# 09-_CAN.net
KiCad netlist of a schematic drawn in Altium Designer
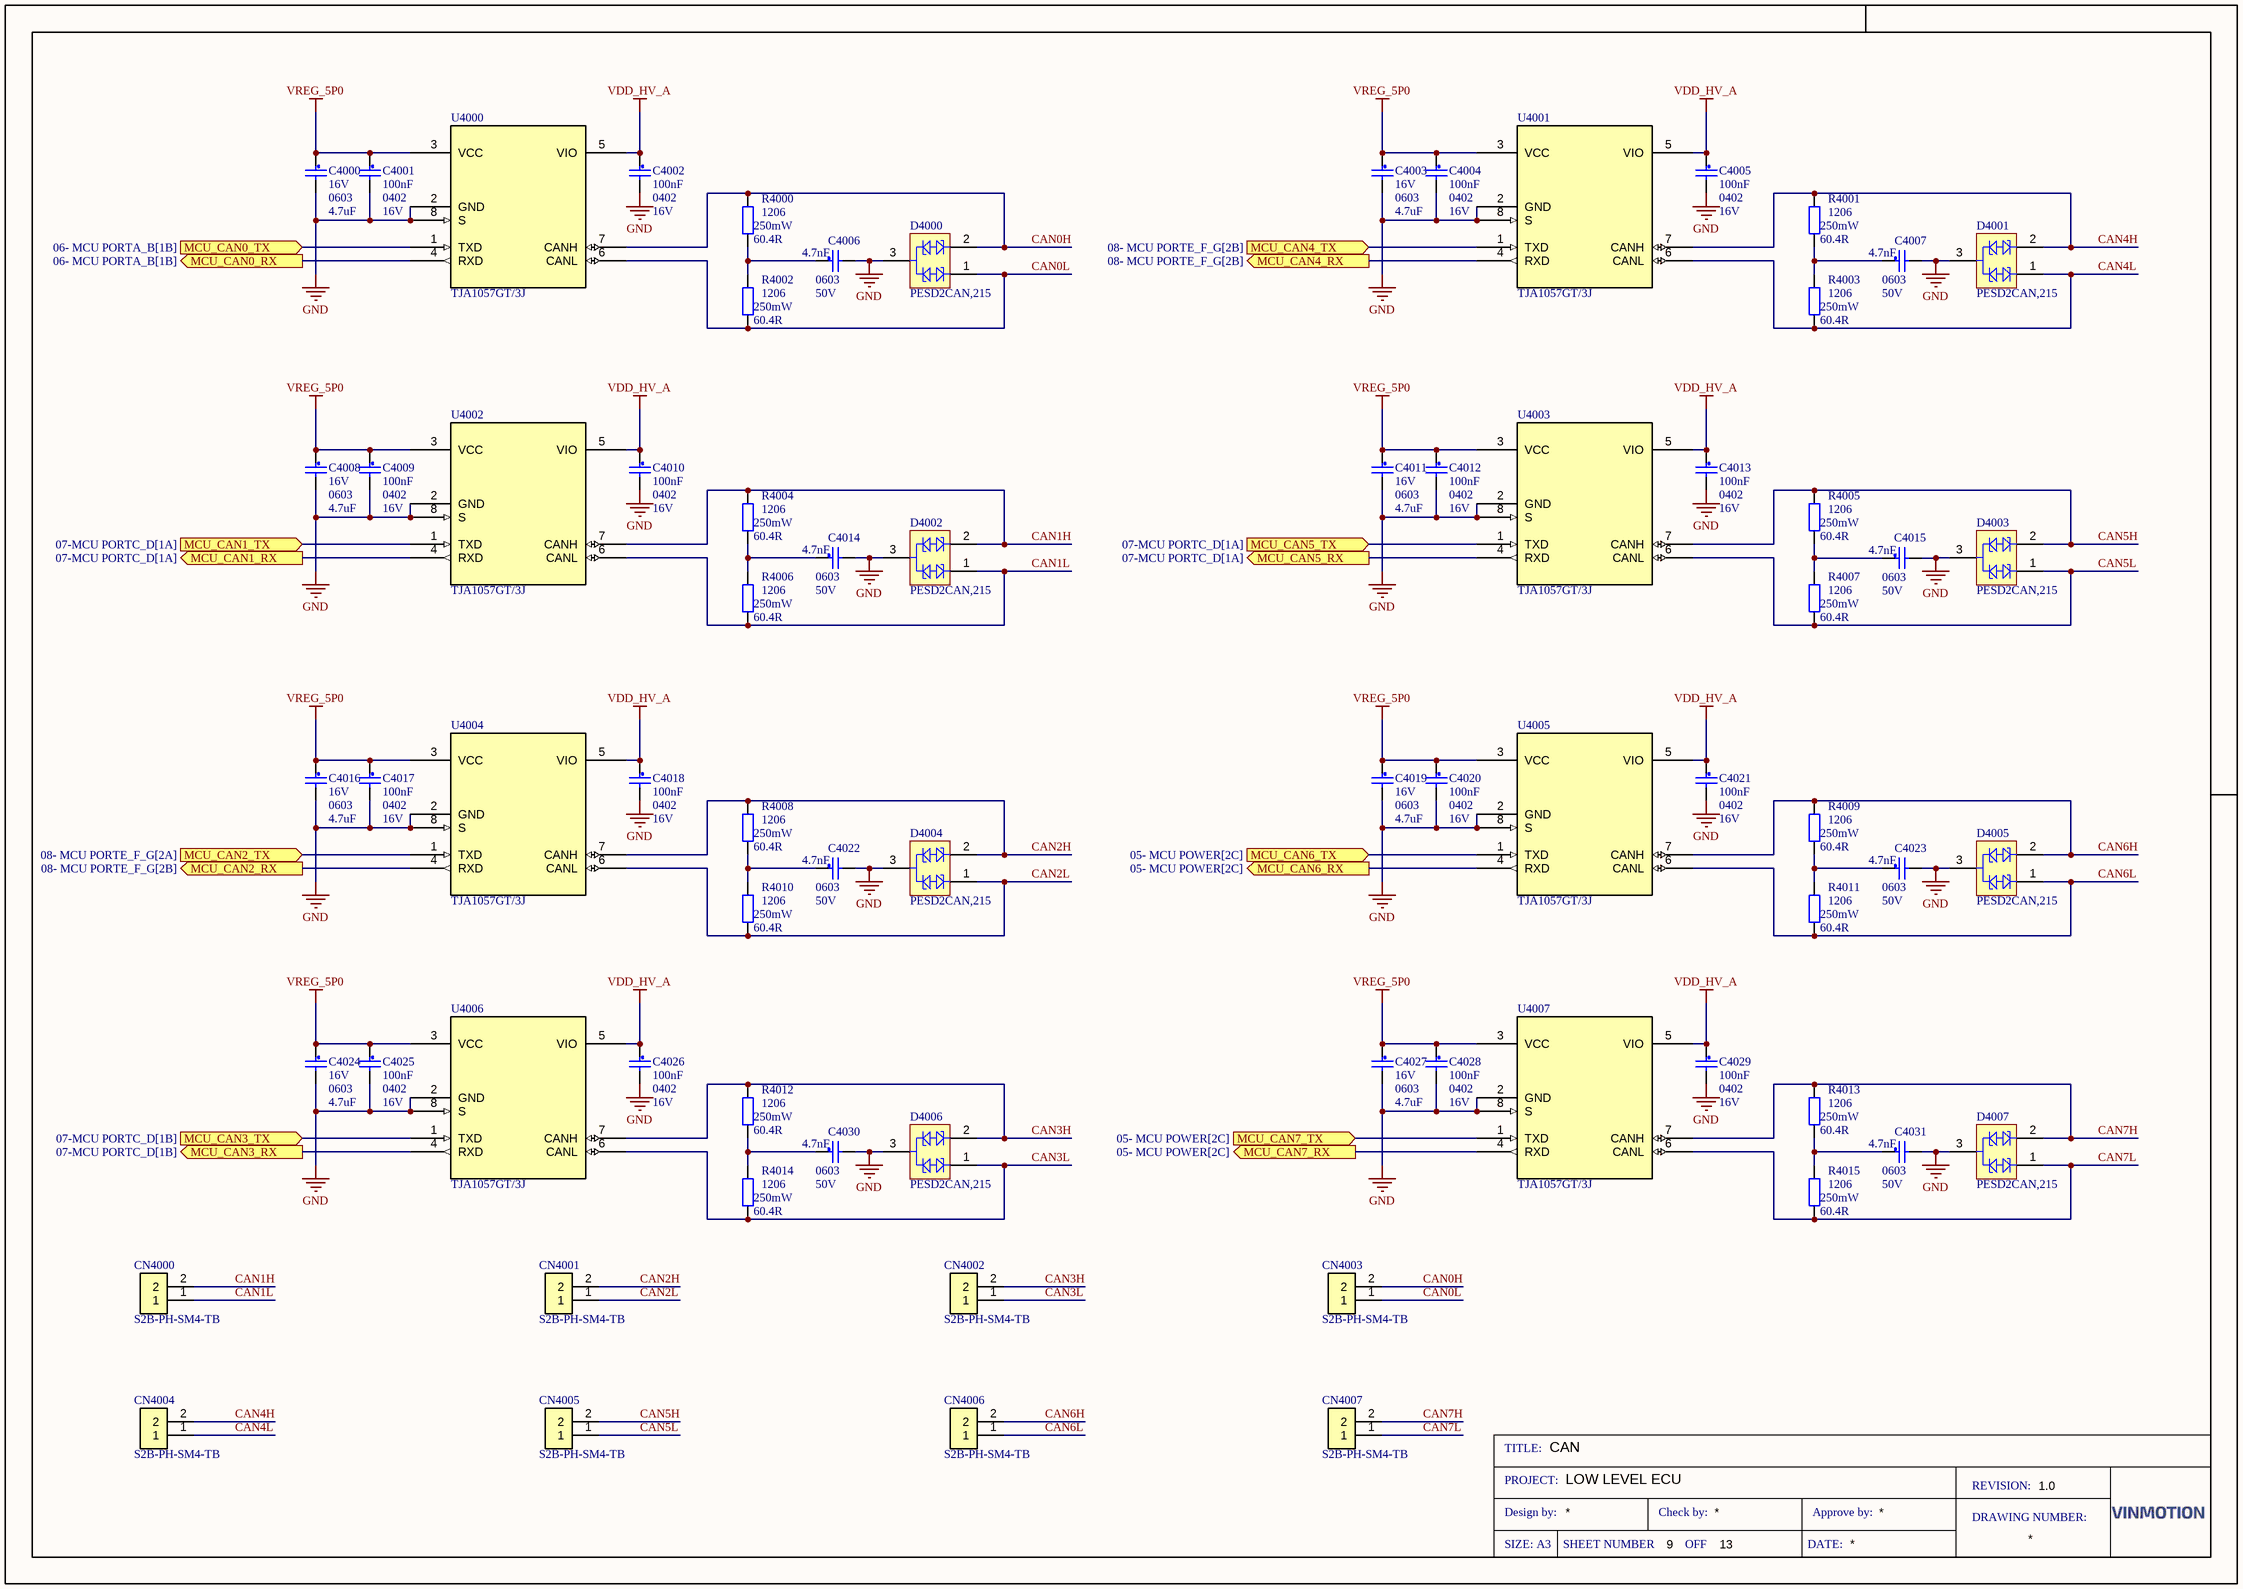
[diagram p0: 09- CAN.SchDoc]

(export (version "E")
  (design (tool "Eeschema 10.0.6"))
  (components
    (comp (ref "C4000")
      (value "GRT188C81C475KE13D")
      (footprint "CAP0603")
      (description "CAP CER 4.7uF 16V 10% X6S 0603 SMD")
      (fields
        (field (name "TOLERANCE") "10%")
        (field (name "VOLTAGE RATING") "16V")
        (field (name "CASE/PACKAGE") "0603")
        (field (name "CAPACITANCE") "4.7uF")
      )
      (libsource (lib "VMO_Lib") (part "CMP-00351-2"))
    )
    (comp (ref "C4001")
      (value "0402YC104KAT2A")
      (footprint "CAP0402")
      (description "CAP CER 0.1UF 16V X7R 0402")
      (fields
        (field (name "CAPACITANCE") "100nF")
        (field (name "CASE/PACKAGE") "0402")
        (field (name "VOLTAGE RATING (DC)") "16V")
      )
      (libsource (lib "VMO_Lib") (part "CMP-00988-1"))
    )
    (comp (ref "C4002")
      (value "0402YC104KAT2A")
      (footprint "CAP0402")
      (description "CAP CER 0.1UF 16V X7R 0402")
      (fields
        (field (name "CAPACITANCE") "100nF")
        (field (name "CASE/PACKAGE") "0402")
        (field (name "VOLTAGE RATING (DC)") "16V")
      )
      (libsource (lib "VMO_Lib") (part "CMP-00988-1"))
    )
    (comp (ref "C4003")
      (value "GRT188C81C475KE13D")
      (footprint "CAP0603")
      (description "CAP CER 4.7uF 16V 10% X6S 0603 SMD")
      (fields
        (field (name "TOLERANCE") "10%")
        (field (name "VOLTAGE RATING") "16V")
        (field (name "CASE/PACKAGE") "0603")
        (field (name "CAPACITANCE") "4.7uF")
      )
      (libsource (lib "VMO_Lib") (part "CMP-00351-2"))
    )
    (comp (ref "C4004")
      (value "0402YC104KAT2A")
      (footprint "CAP0402")
      (description "CAP CER 0.1UF 16V X7R 0402")
      (fields
        (field (name "CAPACITANCE") "100nF")
        (field (name "CASE/PACKAGE") "0402")
        (field (name "VOLTAGE RATING (DC)") "16V")
      )
      (libsource (lib "VMO_Lib") (part "CMP-00988-1"))
    )
    (comp (ref "C4005")
      (value "0402YC104KAT2A")
      (footprint "CAP0402")
      (description "CAP CER 0.1UF 16V X7R 0402")
      (fields
        (field (name "CAPACITANCE") "100nF")
        (field (name "CASE/PACKAGE") "0402")
        (field (name "VOLTAGE RATING (DC)") "16V")
      )
      (libsource (lib "VMO_Lib") (part "CMP-00988-1"))
    )
    (comp (ref "C4006")
      (value "CL10B472KB8WPNC")
      (footprint "CAP0603")
      (description "CAP CER 4700PF 50V X7R 0603")
      (fields
        (field (name "TOLERANCE") "10%")
        (field (name "CASE CODE (IMPERIAL)") "0603")
        (field (name "VOLTAGE RATING") "50V")
        (field (name "CAPACITANCE") "4.7nF")
      )
      (libsource (lib "VMO_Lib") (part "CMP-00892-1"))
    )
    (comp (ref "C4007")
      (value "CL10B472KB8WPNC")
      (footprint "CAP0603")
      (description "CAP CER 4700PF 50V X7R 0603")
      (fields
        (field (name "TOLERANCE") "10%")
        (field (name "CASE CODE (IMPERIAL)") "0603")
        (field (name "VOLTAGE RATING") "50V")
        (field (name "CAPACITANCE") "4.7nF")
      )
      (libsource (lib "VMO_Lib") (part "CMP-00892-1"))
    )
    (comp (ref "C4008")
      (value "GRT188C81C475KE13D")
      (footprint "CAP0603")
      (description "CAP CER 4.7uF 16V 10% X6S 0603 SMD")
      (fields
        (field (name "TOLERANCE") "10%")
        (field (name "VOLTAGE RATING") "16V")
        (field (name "CASE/PACKAGE") "0603")
        (field (name "CAPACITANCE") "4.7uF")
      )
      (libsource (lib "VMO_Lib") (part "CMP-00351-2"))
    )
    (comp (ref "C4009")
      (value "0402YC104KAT2A")
      (footprint "CAP0402")
      (description "CAP CER 0.1UF 16V X7R 0402")
      (fields
        (field (name "CAPACITANCE") "100nF")
        (field (name "CASE/PACKAGE") "0402")
        (field (name "VOLTAGE RATING (DC)") "16V")
      )
      (libsource (lib "VMO_Lib") (part "CMP-00988-1"))
    )
    (comp (ref "C4010")
      (value "0402YC104KAT2A")
      (footprint "CAP0402")
      (description "CAP CER 0.1UF 16V X7R 0402")
      (fields
        (field (name "CAPACITANCE") "100nF")
        (field (name "CASE/PACKAGE") "0402")
        (field (name "VOLTAGE RATING (DC)") "16V")
      )
      (libsource (lib "VMO_Lib") (part "CMP-00988-1"))
    )
    (comp (ref "C4011")
      (value "GRT188C81C475KE13D")
      (footprint "CAP0603")
      (description "CAP CER 4.7uF 16V 10% X6S 0603 SMD")
      (fields
        (field (name "TOLERANCE") "10%")
        (field (name "VOLTAGE RATING") "16V")
        (field (name "CASE/PACKAGE") "0603")
        (field (name "CAPACITANCE") "4.7uF")
      )
      (libsource (lib "VMO_Lib") (part "CMP-00351-2"))
    )
    (comp (ref "C4012")
      (value "0402YC104KAT2A")
      (footprint "CAP0402")
      (description "CAP CER 0.1UF 16V X7R 0402")
      (fields
        (field (name "CAPACITANCE") "100nF")
        (field (name "CASE/PACKAGE") "0402")
        (field (name "VOLTAGE RATING (DC)") "16V")
      )
      (libsource (lib "VMO_Lib") (part "CMP-00988-1"))
    )
    (comp (ref "C4013")
      (value "0402YC104KAT2A")
      (footprint "CAP0402")
      (description "CAP CER 0.1UF 16V X7R 0402")
      (fields
        (field (name "CAPACITANCE") "100nF")
        (field (name "CASE/PACKAGE") "0402")
        (field (name "VOLTAGE RATING (DC)") "16V")
      )
      (libsource (lib "VMO_Lib") (part "CMP-00988-1"))
    )
    (comp (ref "C4014")
      (value "CL10B472KB8WPNC")
      (footprint "CAP0603")
      (description "CAP CER 4700PF 50V X7R 0603")
      (fields
        (field (name "TOLERANCE") "10%")
        (field (name "CASE CODE (IMPERIAL)") "0603")
        (field (name "VOLTAGE RATING") "50V")
        (field (name "CAPACITANCE") "4.7nF")
      )
      (libsource (lib "VMO_Lib") (part "CMP-00892-1"))
    )
    (comp (ref "C4015")
      (value "CL10B472KB8WPNC")
      (footprint "CAP0603")
      (description "CAP CER 4700PF 50V X7R 0603")
      (fields
        (field (name "TOLERANCE") "10%")
        (field (name "CASE CODE (IMPERIAL)") "0603")
        (field (name "VOLTAGE RATING") "50V")
        (field (name "CAPACITANCE") "4.7nF")
      )
      (libsource (lib "VMO_Lib") (part "CMP-00892-1"))
    )
    (comp (ref "C4016")
      (value "GRT188C81C475KE13D")
      (footprint "CAP0603")
      (description "CAP CER 4.7uF 16V 10% X6S 0603 SMD")
      (fields
        (field (name "TOLERANCE") "10%")
        (field (name "VOLTAGE RATING") "16V")
        (field (name "CASE/PACKAGE") "0603")
        (field (name "CAPACITANCE") "4.7uF")
      )
      (libsource (lib "VMO_Lib") (part "CMP-00351-2"))
    )
    (comp (ref "C4017")
      (value "0402YC104KAT2A")
      (footprint "CAP0402")
      (description "CAP CER 0.1UF 16V X7R 0402")
      (fields
        (field (name "CAPACITANCE") "100nF")
        (field (name "CASE/PACKAGE") "0402")
        (field (name "VOLTAGE RATING (DC)") "16V")
      )
      (libsource (lib "VMO_Lib") (part "CMP-00988-1"))
    )
    (comp (ref "C4018")
      (value "0402YC104KAT2A")
      (footprint "CAP0402")
      (description "CAP CER 0.1UF 16V X7R 0402")
      (fields
        (field (name "CAPACITANCE") "100nF")
        (field (name "CASE/PACKAGE") "0402")
        (field (name "VOLTAGE RATING (DC)") "16V")
      )
      (libsource (lib "VMO_Lib") (part "CMP-00988-1"))
    )
    (comp (ref "C4019")
      (value "GRT188C81C475KE13D")
      (footprint "CAP0603")
      (description "CAP CER 4.7uF 16V 10% X6S 0603 SMD")
      (fields
        (field (name "TOLERANCE") "10%")
        (field (name "VOLTAGE RATING") "16V")
        (field (name "CASE/PACKAGE") "0603")
        (field (name "CAPACITANCE") "4.7uF")
      )
      (libsource (lib "VMO_Lib") (part "CMP-00351-2"))
    )
    (comp (ref "C4020")
      (value "0402YC104KAT2A")
      (footprint "CAP0402")
      (description "CAP CER 0.1UF 16V X7R 0402")
      (fields
        (field (name "CAPACITANCE") "100nF")
        (field (name "CASE/PACKAGE") "0402")
        (field (name "VOLTAGE RATING (DC)") "16V")
      )
      (libsource (lib "VMO_Lib") (part "CMP-00988-1"))
    )
    (comp (ref "C4021")
      (value "0402YC104KAT2A")
      (footprint "CAP0402")
      (description "CAP CER 0.1UF 16V X7R 0402")
      (fields
        (field (name "CAPACITANCE") "100nF")
        (field (name "CASE/PACKAGE") "0402")
        (field (name "VOLTAGE RATING (DC)") "16V")
      )
      (libsource (lib "VMO_Lib") (part "CMP-00988-1"))
    )
    (comp (ref "C4022")
      (value "CL10B472KB8WPNC")
      (footprint "CAP0603")
      (description "CAP CER 4700PF 50V X7R 0603")
      (fields
        (field (name "TOLERANCE") "10%")
        (field (name "CASE CODE (IMPERIAL)") "0603")
        (field (name "VOLTAGE RATING") "50V")
        (field (name "CAPACITANCE") "4.7nF")
      )
      (libsource (lib "VMO_Lib") (part "CMP-00892-1"))
    )
    (comp (ref "C4023")
      (value "CL10B472KB8WPNC")
      (footprint "CAP0603")
      (description "CAP CER 4700PF 50V X7R 0603")
      (fields
        (field (name "TOLERANCE") "10%")
        (field (name "CASE CODE (IMPERIAL)") "0603")
        (field (name "VOLTAGE RATING") "50V")
        (field (name "CAPACITANCE") "4.7nF")
      )
      (libsource (lib "VMO_Lib") (part "CMP-00892-1"))
    )
    (comp (ref "C4024")
      (value "GRT188C81C475KE13D")
      (footprint "CAP0603")
      (description "CAP CER 4.7uF 16V 10% X6S 0603 SMD")
      (fields
        (field (name "TOLERANCE") "10%")
        (field (name "VOLTAGE RATING") "16V")
        (field (name "CASE/PACKAGE") "0603")
        (field (name "CAPACITANCE") "4.7uF")
      )
      (libsource (lib "VMO_Lib") (part "CMP-00351-2"))
    )
    (comp (ref "C4025")
      (value "0402YC104KAT2A")
      (footprint "CAP0402")
      (description "CAP CER 0.1UF 16V X7R 0402")
      (fields
        (field (name "CAPACITANCE") "100nF")
        (field (name "CASE/PACKAGE") "0402")
        (field (name "VOLTAGE RATING (DC)") "16V")
      )
      (libsource (lib "VMO_Lib") (part "CMP-00988-1"))
    )
    (comp (ref "C4026")
      (value "0402YC104KAT2A")
      (footprint "CAP0402")
      (description "CAP CER 0.1UF 16V X7R 0402")
      (fields
        (field (name "CAPACITANCE") "100nF")
        (field (name "CASE/PACKAGE") "0402")
        (field (name "VOLTAGE RATING (DC)") "16V")
      )
      (libsource (lib "VMO_Lib") (part "CMP-00988-1"))
    )
    (comp (ref "C4027")
      (value "GRT188C81C475KE13D")
      (footprint "CAP0603")
      (description "CAP CER 4.7uF 16V 10% X6S 0603 SMD")
      (fields
        (field (name "TOLERANCE") "10%")
        (field (name "VOLTAGE RATING") "16V")
        (field (name "CASE/PACKAGE") "0603")
        (field (name "CAPACITANCE") "4.7uF")
      )
      (libsource (lib "VMO_Lib") (part "CMP-00351-2"))
    )
    (comp (ref "C4028")
      (value "0402YC104KAT2A")
      (footprint "CAP0402")
      (description "CAP CER 0.1UF 16V X7R 0402")
      (fields
        (field (name "CAPACITANCE") "100nF")
        (field (name "CASE/PACKAGE") "0402")
        (field (name "VOLTAGE RATING (DC)") "16V")
      )
      (libsource (lib "VMO_Lib") (part "CMP-00988-1"))
    )
    (comp (ref "C4029")
      (value "0402YC104KAT2A")
      (footprint "CAP0402")
      (description "CAP CER 0.1UF 16V X7R 0402")
      (fields
        (field (name "CAPACITANCE") "100nF")
        (field (name "CASE/PACKAGE") "0402")
        (field (name "VOLTAGE RATING (DC)") "16V")
      )
      (libsource (lib "VMO_Lib") (part "CMP-00988-1"))
    )
    (comp (ref "C4030")
      (value "CL10B472KB8WPNC")
      (footprint "CAP0603")
      (description "CAP CER 4700PF 50V X7R 0603")
      (fields
        (field (name "TOLERANCE") "10%")
        (field (name "CASE CODE (IMPERIAL)") "0603")
        (field (name "VOLTAGE RATING") "50V")
        (field (name "CAPACITANCE") "4.7nF")
      )
      (libsource (lib "VMO_Lib") (part "CMP-00892-1"))
    )
    (comp (ref "C4031")
      (value "CL10B472KB8WPNC")
      (footprint "CAP0603")
      (description "CAP CER 4700PF 50V X7R 0603")
      (fields
        (field (name "TOLERANCE") "10%")
        (field (name "CASE CODE (IMPERIAL)") "0603")
        (field (name "VOLTAGE RATING") "50V")
        (field (name "CAPACITANCE") "4.7nF")
      )
      (libsource (lib "VMO_Lib") (part "CMP-00892-1"))
    )
    (comp (ref "CN4000")
      (value "S2B-PH-SM4-TB")
      (footprint "S2B-PH-SM4-TB")
      (description "CONN HEADER SMD R/A 2POS 2MM")
      (fields (field (name "MANUFACTURER") "JST") (field (name "MANUFACTURER PART NUMBER") "S2BPHSM4TBLFSN"))
      (libsource (lib "VMO_Lib") (part "CMP-01142-1"))
    )
    (comp (ref "CN4001")
      (value "S2B-PH-SM4-TB")
      (footprint "S2B-PH-SM4-TB")
      (description "CONN HEADER SMD R/A 2POS 2MM")
      (fields (field (name "MANUFACTURER") "JST") (field (name "MANUFACTURER PART NUMBER") "S2BPHSM4TBLFSN"))
      (libsource (lib "VMO_Lib") (part "CMP-01142-1"))
    )
    (comp (ref "CN4002")
      (value "S2B-PH-SM4-TB")
      (footprint "S2B-PH-SM4-TB")
      (description "CONN HEADER SMD R/A 2POS 2MM")
      (fields (field (name "MANUFACTURER") "JST") (field (name "MANUFACTURER PART NUMBER") "S2BPHSM4TBLFSN"))
      (libsource (lib "VMO_Lib") (part "CMP-01142-1"))
    )
    (comp (ref "CN4003")
      (value "S2B-PH-SM4-TB")
      (footprint "S2B-PH-SM4-TB")
      (description "CONN HEADER SMD R/A 2POS 2MM")
      (fields (field (name "MANUFACTURER") "JST") (field (name "MANUFACTURER PART NUMBER") "S2BPHSM4TBLFSN"))
      (libsource (lib "VMO_Lib") (part "CMP-01142-1"))
    )
    (comp (ref "CN4004")
      (value "S2B-PH-SM4-TB")
      (footprint "S2B-PH-SM4-TB")
      (description "CONN HEADER SMD R/A 2POS 2MM")
      (fields (field (name "MANUFACTURER") "JST") (field (name "MANUFACTURER PART NUMBER") "S2BPHSM4TBLFSN"))
      (libsource (lib "VMO_Lib") (part "CMP-01142-1"))
    )
    (comp (ref "CN4005")
      (value "S2B-PH-SM4-TB")
      (footprint "S2B-PH-SM4-TB")
      (description "CONN HEADER SMD R/A 2POS 2MM")
      (fields (field (name "MANUFACTURER") "JST") (field (name "MANUFACTURER PART NUMBER") "S2BPHSM4TBLFSN"))
      (libsource (lib "VMO_Lib") (part "CMP-01142-1"))
    )
    (comp (ref "CN4006")
      (value "S2B-PH-SM4-TB")
      (footprint "S2B-PH-SM4-TB")
      (description "CONN HEADER SMD R/A 2POS 2MM")
      (fields (field (name "MANUFACTURER") "JST") (field (name "MANUFACTURER PART NUMBER") "S2BPHSM4TBLFSN"))
      (libsource (lib "VMO_Lib") (part "CMP-01142-1"))
    )
    (comp (ref "CN4007")
      (value "S2B-PH-SM4-TB")
      (footprint "S2B-PH-SM4-TB")
      (description "CONN HEADER SMD R/A 2POS 2MM")
      (fields (field (name "MANUFACTURER") "JST") (field (name "MANUFACTURER PART NUMBER") "S2BPHSM4TBLFSN"))
      (libsource (lib "VMO_Lib") (part "CMP-01142-1"))
    )
    (comp (ref "D4000")
      (value "PESD2CAN,215")
      (footprint "NEXPERIA_PESD2CAN,215_N")
      (description "DIODE TVS 24VWM 41VC SOT-23-3")
      (libsource (lib "VMO_Lib") (part "CMP-ROOT-0006-8"))
    )
    (comp (ref "D4001")
      (value "PESD2CAN,215")
      (footprint "NEXPERIA_PESD2CAN,215_N")
      (description "DIODE TVS 24VWM 41VC SOT-23-3")
      (libsource (lib "VMO_Lib") (part "CMP-ROOT-0006-8"))
    )
    (comp (ref "D4002")
      (value "PESD2CAN,215")
      (footprint "NEXPERIA_PESD2CAN,215_N")
      (description "DIODE TVS 24VWM 41VC SOT-23-3")
      (libsource (lib "VMO_Lib") (part "CMP-ROOT-0006-8"))
    )
    (comp (ref "D4003")
      (value "PESD2CAN,215")
      (footprint "NEXPERIA_PESD2CAN,215_N")
      (description "DIODE TVS 24VWM 41VC SOT-23-3")
      (libsource (lib "VMO_Lib") (part "CMP-ROOT-0006-8"))
    )
    (comp (ref "D4004")
      (value "PESD2CAN,215")
      (footprint "NEXPERIA_PESD2CAN,215_N")
      (description "DIODE TVS 24VWM 41VC SOT-23-3")
      (libsource (lib "VMO_Lib") (part "CMP-ROOT-0006-8"))
    )
    (comp (ref "D4005")
      (value "PESD2CAN,215")
      (footprint "NEXPERIA_PESD2CAN,215_N")
      (description "DIODE TVS 24VWM 41VC SOT-23-3")
      (libsource (lib "VMO_Lib") (part "CMP-ROOT-0006-8"))
    )
    (comp (ref "D4006")
      (value "PESD2CAN,215")
      (footprint "NEXPERIA_PESD2CAN,215_N")
      (description "DIODE TVS 24VWM 41VC SOT-23-3")
      (libsource (lib "VMO_Lib") (part "CMP-ROOT-0006-8"))
    )
    (comp (ref "D4007")
      (value "PESD2CAN,215")
      (footprint "NEXPERIA_PESD2CAN,215_N")
      (description "DIODE TVS 24VWM 41VC SOT-23-3")
      (libsource (lib "VMO_Lib") (part "CMP-ROOT-0006-8"))
    )
    (comp (ref "R4000")
      (value "RMCF1206FT60R4")
      (footprint "RES1206")
      (description "RES 60.4R 1/4W 1% 1206 SMD")
      (fields
        (field (name "MAX POWER DISSIPATION") "250mW")
        (field (name "TOLERANCE") "1%")
        (field (name "RESISTANCE") "60.4R")
        (field (name "CASE/PACKAGE") "1206")
      )
      (libsource (lib "VMO_Lib") (part "CMP-00099-3"))
    )
    (comp (ref "R4001")
      (value "RMCF1206FT60R4")
      (footprint "RES1206")
      (description "RES 60.4R 1/4W 1% 1206 SMD")
      (fields
        (field (name "MAX POWER DISSIPATION") "250mW")
        (field (name "TOLERANCE") "1%")
        (field (name "RESISTANCE") "60.4R")
        (field (name "CASE/PACKAGE") "1206")
      )
      (libsource (lib "VMO_Lib") (part "CMP-00099-3"))
    )
    (comp (ref "R4002")
      (value "RMCF1206FT60R4")
      (footprint "RES1206")
      (description "RES 60.4R 1/4W 1% 1206 SMD")
      (fields
        (field (name "MAX POWER DISSIPATION") "250mW")
        (field (name "TOLERANCE") "1%")
        (field (name "RESISTANCE") "60.4R")
        (field (name "CASE/PACKAGE") "1206")
      )
      (libsource (lib "VMO_Lib") (part "CMP-00099-3"))
    )
    (comp (ref "R4003")
      (value "RMCF1206FT60R4")
      (footprint "RES1206")
      (description "RES 60.4R 1/4W 1% 1206 SMD")
      (fields
        (field (name "MAX POWER DISSIPATION") "250mW")
        (field (name "TOLERANCE") "1%")
        (field (name "RESISTANCE") "60.4R")
        (field (name "CASE/PACKAGE") "1206")
      )
      (libsource (lib "VMO_Lib") (part "CMP-00099-3"))
    )
    (comp (ref "R4004")
      (value "RMCF1206FT60R4")
      (footprint "RES1206")
      (description "RES 60.4R 1/4W 1% 1206 SMD")
      (fields
        (field (name "MAX POWER DISSIPATION") "250mW")
        (field (name "TOLERANCE") "1%")
        (field (name "RESISTANCE") "60.4R")
        (field (name "CASE/PACKAGE") "1206")
      )
      (libsource (lib "VMO_Lib") (part "CMP-00099-3"))
    )
    (comp (ref "R4005")
      (value "RMCF1206FT60R4")
      (footprint "RES1206")
      (description "RES 60.4R 1/4W 1% 1206 SMD")
      (fields
        (field (name "MAX POWER DISSIPATION") "250mW")
        (field (name "TOLERANCE") "1%")
        (field (name "RESISTANCE") "60.4R")
        (field (name "CASE/PACKAGE") "1206")
      )
      (libsource (lib "VMO_Lib") (part "CMP-00099-3"))
    )
    (comp (ref "R4006")
      (value "RMCF1206FT60R4")
      (footprint "RES1206")
      (description "RES 60.4R 1/4W 1% 1206 SMD")
      (fields
        (field (name "MAX POWER DISSIPATION") "250mW")
        (field (name "TOLERANCE") "1%")
        (field (name "RESISTANCE") "60.4R")
        (field (name "CASE/PACKAGE") "1206")
      )
      (libsource (lib "VMO_Lib") (part "CMP-00099-3"))
    )
    (comp (ref "R4007")
      (value "RMCF1206FT60R4")
      (footprint "RES1206")
      (description "RES 60.4R 1/4W 1% 1206 SMD")
      (fields
        (field (name "MAX POWER DISSIPATION") "250mW")
        (field (name "TOLERANCE") "1%")
        (field (name "RESISTANCE") "60.4R")
        (field (name "CASE/PACKAGE") "1206")
      )
      (libsource (lib "VMO_Lib") (part "CMP-00099-3"))
    )
    (comp (ref "R4008")
      (value "RMCF1206FT60R4")
      (footprint "RES1206")
      (description "RES 60.4R 1/4W 1% 1206 SMD")
      (fields
        (field (name "MAX POWER DISSIPATION") "250mW")
        (field (name "TOLERANCE") "1%")
        (field (name "RESISTANCE") "60.4R")
        (field (name "CASE/PACKAGE") "1206")
      )
      (libsource (lib "VMO_Lib") (part "CMP-00099-3"))
    )
    (comp (ref "R4009")
      (value "RMCF1206FT60R4")
      (footprint "RES1206")
      (description "RES 60.4R 1/4W 1% 1206 SMD")
      (fields
        (field (name "MAX POWER DISSIPATION") "250mW")
        (field (name "TOLERANCE") "1%")
        (field (name "RESISTANCE") "60.4R")
        (field (name "CASE/PACKAGE") "1206")
      )
      (libsource (lib "VMO_Lib") (part "CMP-00099-3"))
    )
    (comp (ref "R4010")
      (value "RMCF1206FT60R4")
      (footprint "RES1206")
      (description "RES 60.4R 1/4W 1% 1206 SMD")
      (fields
        (field (name "MAX POWER DISSIPATION") "250mW")
        (field (name "TOLERANCE") "1%")
        (field (name "RESISTANCE") "60.4R")
        (field (name "CASE/PACKAGE") "1206")
      )
      (libsource (lib "VMO_Lib") (part "CMP-00099-3"))
    )
    (comp (ref "R4011")
      (value "RMCF1206FT60R4")
      (footprint "RES1206")
      (description "RES 60.4R 1/4W 1% 1206 SMD")
      (fields
        (field (name "MAX POWER DISSIPATION") "250mW")
        (field (name "TOLERANCE") "1%")
        (field (name "RESISTANCE") "60.4R")
        (field (name "CASE/PACKAGE") "1206")
      )
      (libsource (lib "VMO_Lib") (part "CMP-00099-3"))
    )
    (comp (ref "R4012")
      (value "RMCF1206FT60R4")
      (footprint "RES1206")
      (description "RES 60.4R 1/4W 1% 1206 SMD")
      (fields
        (field (name "MAX POWER DISSIPATION") "250mW")
        (field (name "TOLERANCE") "1%")
        (field (name "RESISTANCE") "60.4R")
        (field (name "CASE/PACKAGE") "1206")
      )
      (libsource (lib "VMO_Lib") (part "CMP-00099-3"))
    )
    (comp (ref "R4013")
      (value "RMCF1206FT60R4")
      (footprint "RES1206")
      (description "RES 60.4R 1/4W 1% 1206 SMD")
      (fields
        (field (name "MAX POWER DISSIPATION") "250mW")
        (field (name "TOLERANCE") "1%")
        (field (name "RESISTANCE") "60.4R")
        (field (name "CASE/PACKAGE") "1206")
      )
      (libsource (lib "VMO_Lib") (part "CMP-00099-3"))
    )
    (comp (ref "R4014")
      (value "RMCF1206FT60R4")
      (footprint "RES1206")
      (description "RES 60.4R 1/4W 1% 1206 SMD")
      (fields
        (field (name "MAX POWER DISSIPATION") "250mW")
        (field (name "TOLERANCE") "1%")
        (field (name "RESISTANCE") "60.4R")
        (field (name "CASE/PACKAGE") "1206")
      )
      (libsource (lib "VMO_Lib") (part "CMP-00099-3"))
    )
    (comp (ref "R4015")
      (value "RMCF1206FT60R4")
      (footprint "RES1206")
      (description "RES 60.4R 1/4W 1% 1206 SMD")
      (fields
        (field (name "MAX POWER DISSIPATION") "250mW")
        (field (name "TOLERANCE") "1%")
        (field (name "RESISTANCE") "60.4R")
        (field (name "CASE/PACKAGE") "1206")
      )
      (libsource (lib "VMO_Lib") (part "CMP-00099-3"))
    )
    (comp (ref "U4000")
      (value "TJA1057GT/3J")
      (footprint "SOIC127P590X175-8N")
      (description "1/1 Transceiver Half CANbus 8-SO")
      (fields (field (name "MANUFACTURER") "NXP Semiconductors"))
      (libsource (lib "VMO_Lib") (part "CMP-01192-1"))
    )
    (comp (ref "U4001")
      (value "TJA1057GT/3J")
      (footprint "SOIC127P590X175-8N")
      (description "1/1 Transceiver Half CANbus 8-SO")
      (fields (field (name "MANUFACTURER") "NXP Semiconductors"))
      (libsource (lib "VMO_Lib") (part "CMP-01192-1"))
    )
    (comp (ref "U4002")
      (value "TJA1057GT/3J")
      (footprint "SOIC127P590X175-8N")
      (description "1/1 Transceiver Half CANbus 8-SO")
      (fields (field (name "MANUFACTURER") "NXP Semiconductors"))
      (libsource (lib "VMO_Lib") (part "CMP-01192-1"))
    )
    (comp (ref "U4003")
      (value "TJA1057GT/3J")
      (footprint "SOIC127P590X175-8N")
      (description "1/1 Transceiver Half CANbus 8-SO")
      (fields (field (name "MANUFACTURER") "NXP Semiconductors"))
      (libsource (lib "VMO_Lib") (part "CMP-01192-1"))
    )
    (comp (ref "U4004")
      (value "TJA1057GT/3J")
      (footprint "SOIC127P590X175-8N")
      (description "1/1 Transceiver Half CANbus 8-SO")
      (fields (field (name "MANUFACTURER") "NXP Semiconductors"))
      (libsource (lib "VMO_Lib") (part "CMP-01192-1"))
    )
    (comp (ref "U4005")
      (value "TJA1057GT/3J")
      (footprint "SOIC127P590X175-8N")
      (description "1/1 Transceiver Half CANbus 8-SO")
      (fields (field (name "MANUFACTURER") "NXP Semiconductors"))
      (libsource (lib "VMO_Lib") (part "CMP-01192-1"))
    )
    (comp (ref "U4006")
      (value "TJA1057GT/3J")
      (footprint "SOIC127P590X175-8N")
      (description "1/1 Transceiver Half CANbus 8-SO")
      (fields (field (name "MANUFACTURER") "NXP Semiconductors"))
      (libsource (lib "VMO_Lib") (part "CMP-01192-1"))
    )
    (comp (ref "U4007")
      (value "TJA1057GT/3J")
      (footprint "SOIC127P590X175-8N")
      (description "1/1 Transceiver Half CANbus 8-SO")
      (fields (field (name "MANUFACTURER") "NXP Semiconductors"))
      (libsource (lib "VMO_Lib") (part "CMP-01192-1"))
    )
  )
  (nets
    (net (code "1") (name "/CAN0H") (class "Default")
      (node (ref "CN4003") (pin "2") (pinfunction "2_2") (pintype "passive"))
      (node (ref "D4000") (pin "2") (pinfunction "2_2") (pintype "passive"))
      (node (ref "R4000") (pin "1") (pinfunction "1_1") (pintype "passive"))
      (node (ref "U4000") (pin "7") (pinfunction "CANH_7") (pintype "bidirectional"))
    )
    (net (code "2") (name "/CAN0L") (class "Default")
      (node (ref "CN4003") (pin "1") (pinfunction "1_1") (pintype "passive"))
      (node (ref "D4000") (pin "1") (pinfunction "1_1") (pintype "passive"))
      (node (ref "R4002") (pin "2") (pinfunction "2_2") (pintype "passive"))
      (node (ref "U4000") (pin "6") (pinfunction "CANL_6") (pintype "bidirectional"))
    )
    (net (code "3") (name "/CAN1H") (class "Default")
      (node (ref "CN4000") (pin "2") (pinfunction "2_2") (pintype "passive"))
      (node (ref "D4002") (pin "2") (pinfunction "2_2") (pintype "passive"))
      (node (ref "R4004") (pin "1") (pinfunction "1_1") (pintype "passive"))
      (node (ref "U4002") (pin "7") (pinfunction "CANH_7") (pintype "bidirectional"))
    )
    (net (code "4") (name "/CAN1L") (class "Default")
      (node (ref "CN4000") (pin "1") (pinfunction "1_1") (pintype "passive"))
      (node (ref "D4002") (pin "1") (pinfunction "1_1") (pintype "passive"))
      (node (ref "R4006") (pin "2") (pinfunction "2_2") (pintype "passive"))
      (node (ref "U4002") (pin "6") (pinfunction "CANL_6") (pintype "bidirectional"))
    )
    (net (code "5") (name "/CAN2H") (class "Default")
      (node (ref "CN4001") (pin "2") (pinfunction "2_2") (pintype "passive"))
      (node (ref "D4004") (pin "2") (pinfunction "2_2") (pintype "passive"))
      (node (ref "R4008") (pin "1") (pinfunction "1_1") (pintype "passive"))
      (node (ref "U4004") (pin "7") (pinfunction "CANH_7") (pintype "bidirectional"))
    )
    (net (code "6") (name "/CAN2L") (class "Default")
      (node (ref "CN4001") (pin "1") (pinfunction "1_1") (pintype "passive"))
      (node (ref "D4004") (pin "1") (pinfunction "1_1") (pintype "passive"))
      (node (ref "R4010") (pin "2") (pinfunction "2_2") (pintype "passive"))
      (node (ref "U4004") (pin "6") (pinfunction "CANL_6") (pintype "bidirectional"))
    )
    (net (code "7") (name "/CAN3H") (class "Default")
      (node (ref "CN4002") (pin "2") (pinfunction "2_2") (pintype "passive"))
      (node (ref "D4006") (pin "2") (pinfunction "2_2") (pintype "passive"))
      (node (ref "R4012") (pin "1") (pinfunction "1_1") (pintype "passive"))
      (node (ref "U4006") (pin "7") (pinfunction "CANH_7") (pintype "bidirectional"))
    )
    (net (code "8") (name "/CAN3L") (class "Default")
      (node (ref "CN4002") (pin "1") (pinfunction "1_1") (pintype "passive"))
      (node (ref "D4006") (pin "1") (pinfunction "1_1") (pintype "passive"))
      (node (ref "R4014") (pin "2") (pinfunction "2_2") (pintype "passive"))
      (node (ref "U4006") (pin "6") (pinfunction "CANL_6") (pintype "bidirectional"))
    )
    (net (code "9") (name "/CAN4H") (class "Default")
      (node (ref "CN4004") (pin "2") (pinfunction "2_2") (pintype "passive"))
      (node (ref "D4001") (pin "2") (pinfunction "2_2") (pintype "passive"))
      (node (ref "R4001") (pin "1") (pinfunction "1_1") (pintype "passive"))
      (node (ref "U4001") (pin "7") (pinfunction "CANH_7") (pintype "bidirectional"))
    )
    (net (code "10") (name "/CAN4L") (class "Default")
      (node (ref "CN4004") (pin "1") (pinfunction "1_1") (pintype "passive"))
      (node (ref "D4001") (pin "1") (pinfunction "1_1") (pintype "passive"))
      (node (ref "R4003") (pin "2") (pinfunction "2_2") (pintype "passive"))
      (node (ref "U4001") (pin "6") (pinfunction "CANL_6") (pintype "bidirectional"))
    )
    (net (code "11") (name "/CAN5H") (class "Default")
      (node (ref "CN4005") (pin "2") (pinfunction "2_2") (pintype "passive"))
      (node (ref "D4003") (pin "2") (pinfunction "2_2") (pintype "passive"))
      (node (ref "R4005") (pin "1") (pinfunction "1_1") (pintype "passive"))
      (node (ref "U4003") (pin "7") (pinfunction "CANH_7") (pintype "bidirectional"))
    )
    (net (code "12") (name "/CAN5L") (class "Default")
      (node (ref "CN4005") (pin "1") (pinfunction "1_1") (pintype "passive"))
      (node (ref "D4003") (pin "1") (pinfunction "1_1") (pintype "passive"))
      (node (ref "R4007") (pin "2") (pinfunction "2_2") (pintype "passive"))
      (node (ref "U4003") (pin "6") (pinfunction "CANL_6") (pintype "bidirectional"))
    )
    (net (code "13") (name "/CAN6H") (class "Default")
      (node (ref "CN4006") (pin "2") (pinfunction "2_2") (pintype "passive"))
      (node (ref "D4005") (pin "2") (pinfunction "2_2") (pintype "passive"))
      (node (ref "R4009") (pin "1") (pinfunction "1_1") (pintype "passive"))
      (node (ref "U4005") (pin "7") (pinfunction "CANH_7") (pintype "bidirectional"))
    )
    (net (code "14") (name "/CAN6L") (class "Default")
      (node (ref "CN4006") (pin "1") (pinfunction "1_1") (pintype "passive"))
      (node (ref "D4005") (pin "1") (pinfunction "1_1") (pintype "passive"))
      (node (ref "R4011") (pin "2") (pinfunction "2_2") (pintype "passive"))
      (node (ref "U4005") (pin "6") (pinfunction "CANL_6") (pintype "bidirectional"))
    )
    (net (code "15") (name "/CAN7H") (class "Default")
      (node (ref "CN4007") (pin "2") (pinfunction "2_2") (pintype "passive"))
      (node (ref "D4007") (pin "2") (pinfunction "2_2") (pintype "passive"))
      (node (ref "R4013") (pin "1") (pinfunction "1_1") (pintype "passive"))
      (node (ref "U4007") (pin "7") (pinfunction "CANH_7") (pintype "bidirectional"))
    )
    (net (code "16") (name "/CAN7L") (class "Default")
      (node (ref "CN4007") (pin "1") (pinfunction "1_1") (pintype "passive"))
      (node (ref "D4007") (pin "1") (pinfunction "1_1") (pintype "passive"))
      (node (ref "R4015") (pin "2") (pinfunction "2_2") (pintype "passive"))
      (node (ref "U4007") (pin "6") (pinfunction "CANL_6") (pintype "bidirectional"))
    )
    (net (code "17") (name "/MCU_CAN0_RX") (class "Default")
      (node (ref "U4000") (pin "4") (pinfunction "RXD_4") (pintype "output"))
    )
    (net (code "18") (name "/MCU_CAN0_TX") (class "Default")
      (node (ref "U4000") (pin "1") (pinfunction "TXD_1") (pintype "input"))
    )
    (net (code "19") (name "/MCU_CAN1_RX") (class "Default")
      (node (ref "U4002") (pin "4") (pinfunction "RXD_4") (pintype "output"))
    )
    (net (code "20") (name "/MCU_CAN1_TX") (class "Default")
      (node (ref "U4002") (pin "1") (pinfunction "TXD_1") (pintype "input"))
    )
    (net (code "21") (name "/MCU_CAN2_RX") (class "Default")
      (node (ref "U4004") (pin "4") (pinfunction "RXD_4") (pintype "output"))
    )
    (net (code "22") (name "/MCU_CAN2_TX") (class "Default")
      (node (ref "U4004") (pin "1") (pinfunction "TXD_1") (pintype "input"))
    )
    (net (code "23") (name "/MCU_CAN3_RX") (class "Default")
      (node (ref "U4006") (pin "4") (pinfunction "RXD_4") (pintype "output"))
    )
    (net (code "24") (name "/MCU_CAN3_TX") (class "Default")
      (node (ref "U4006") (pin "1") (pinfunction "TXD_1") (pintype "input"))
    )
    (net (code "25") (name "/MCU_CAN4_RX") (class "Default")
      (node (ref "U4001") (pin "4") (pinfunction "RXD_4") (pintype "output"))
    )
    (net (code "26") (name "/MCU_CAN4_TX") (class "Default")
      (node (ref "U4001") (pin "1") (pinfunction "TXD_1") (pintype "input"))
    )
    (net (code "27") (name "/MCU_CAN5_RX") (class "Default")
      (node (ref "U4003") (pin "4") (pinfunction "RXD_4") (pintype "output"))
    )
    (net (code "28") (name "/MCU_CAN5_TX") (class "Default")
      (node (ref "U4003") (pin "1") (pinfunction "TXD_1") (pintype "input"))
    )
    (net (code "29") (name "/MCU_CAN6_RX") (class "Default")
      (node (ref "U4005") (pin "4") (pinfunction "RXD_4") (pintype "output"))
    )
    (net (code "30") (name "/MCU_CAN6_TX") (class "Default")
      (node (ref "U4005") (pin "1") (pinfunction "TXD_1") (pintype "input"))
    )
    (net (code "31") (name "/MCU_CAN7_RX") (class "Default")
      (node (ref "U4007") (pin "4") (pinfunction "RXD_4") (pintype "output"))
    )
    (net (code "32") (name "/MCU_CAN7_TX") (class "Default")
      (node (ref "U4007") (pin "1") (pinfunction "TXD_1") (pintype "input"))
    )
    (net (code "33") (name "GND") (class "Default")
      (node (ref "C4000") (pin "2") (pinfunction "2_2") (pintype "passive"))
      (node (ref "C4001") (pin "2") (pinfunction "2_2") (pintype "passive"))
      (node (ref "C4002") (pin "2") (pinfunction "2_2") (pintype "passive"))
      (node (ref "C4003") (pin "2") (pinfunction "2_2") (pintype "passive"))
      (node (ref "C4004") (pin "2") (pinfunction "2_2") (pintype "passive"))
      (node (ref "C4005") (pin "2") (pinfunction "2_2") (pintype "passive"))
      (node (ref "C4006") (pin "2") (pinfunction "2_2") (pintype "passive"))
      (node (ref "C4007") (pin "2") (pinfunction "2_2") (pintype "passive"))
      (node (ref "C4008") (pin "2") (pinfunction "2_2") (pintype "passive"))
      (node (ref "C4009") (pin "2") (pinfunction "2_2") (pintype "passive"))
      (node (ref "C4010") (pin "2") (pinfunction "2_2") (pintype "passive"))
      (node (ref "C4011") (pin "2") (pinfunction "2_2") (pintype "passive"))
      (node (ref "C4012") (pin "2") (pinfunction "2_2") (pintype "passive"))
      (node (ref "C4013") (pin "2") (pinfunction "2_2") (pintype "passive"))
      (node (ref "C4014") (pin "2") (pinfunction "2_2") (pintype "passive"))
      (node (ref "C4015") (pin "2") (pinfunction "2_2") (pintype "passive"))
      (node (ref "C4016") (pin "2") (pinfunction "2_2") (pintype "passive"))
      (node (ref "C4017") (pin "2") (pinfunction "2_2") (pintype "passive"))
      (node (ref "C4018") (pin "2") (pinfunction "2_2") (pintype "passive"))
      (node (ref "C4019") (pin "2") (pinfunction "2_2") (pintype "passive"))
      (node (ref "C4020") (pin "2") (pinfunction "2_2") (pintype "passive"))
      (node (ref "C4021") (pin "2") (pinfunction "2_2") (pintype "passive"))
      (node (ref "C4022") (pin "2") (pinfunction "2_2") (pintype "passive"))
      (node (ref "C4023") (pin "2") (pinfunction "2_2") (pintype "passive"))
      (node (ref "C4024") (pin "2") (pinfunction "2_2") (pintype "passive"))
      (node (ref "C4025") (pin "2") (pinfunction "2_2") (pintype "passive"))
      (node (ref "C4026") (pin "2") (pinfunction "2_2") (pintype "passive"))
      (node (ref "C4027") (pin "2") (pinfunction "2_2") (pintype "passive"))
      (node (ref "C4028") (pin "2") (pinfunction "2_2") (pintype "passive"))
      (node (ref "C4029") (pin "2") (pinfunction "2_2") (pintype "passive"))
      (node (ref "C4030") (pin "2") (pinfunction "2_2") (pintype "passive"))
      (node (ref "C4031") (pin "2") (pinfunction "2_2") (pintype "passive"))
      (node (ref "D4000") (pin "3") (pinfunction "3_3") (pintype "passive"))
      (node (ref "D4001") (pin "3") (pinfunction "3_3") (pintype "passive"))
      (node (ref "D4002") (pin "3") (pinfunction "3_3") (pintype "passive"))
      (node (ref "D4003") (pin "3") (pinfunction "3_3") (pintype "passive"))
      (node (ref "D4004") (pin "3") (pinfunction "3_3") (pintype "passive"))
      (node (ref "D4005") (pin "3") (pinfunction "3_3") (pintype "passive"))
      (node (ref "D4006") (pin "3") (pinfunction "3_3") (pintype "passive"))
      (node (ref "D4007") (pin "3") (pinfunction "3_3") (pintype "passive"))
      (node (ref "U4000") (pin "2") (pinfunction "GND_2") (pintype "power_in"))
      (node (ref "U4000") (pin "8") (pinfunction "S_8") (pintype "input"))
      (node (ref "U4001") (pin "2") (pinfunction "GND_2") (pintype "power_in"))
      (node (ref "U4001") (pin "8") (pinfunction "S_8") (pintype "input"))
      (node (ref "U4002") (pin "2") (pinfunction "GND_2") (pintype "power_in"))
      (node (ref "U4002") (pin "8") (pinfunction "S_8") (pintype "input"))
      (node (ref "U4003") (pin "2") (pinfunction "GND_2") (pintype "power_in"))
      (node (ref "U4003") (pin "8") (pinfunction "S_8") (pintype "input"))
      (node (ref "U4004") (pin "2") (pinfunction "GND_2") (pintype "power_in"))
      (node (ref "U4004") (pin "8") (pinfunction "S_8") (pintype "input"))
      (node (ref "U4005") (pin "2") (pinfunction "GND_2") (pintype "power_in"))
      (node (ref "U4005") (pin "8") (pinfunction "S_8") (pintype "input"))
      (node (ref "U4006") (pin "2") (pinfunction "GND_2") (pintype "power_in"))
      (node (ref "U4006") (pin "8") (pinfunction "S_8") (pintype "input"))
      (node (ref "U4007") (pin "2") (pinfunction "GND_2") (pintype "power_in"))
      (node (ref "U4007") (pin "8") (pinfunction "S_8") (pintype "input"))
    )
    (net (code "34") (name "Net-(C4006-Pad1)") (class "Default")
      (node (ref "C4006") (pin "1") (pinfunction "1_1") (pintype "passive"))
      (node (ref "R4000") (pin "2") (pinfunction "2_2") (pintype "passive"))
      (node (ref "R4002") (pin "1") (pinfunction "1_1") (pintype "passive"))
    )
    (net (code "35") (name "Net-(C4007-Pad1)") (class "Default")
      (node (ref "C4007") (pin "1") (pinfunction "1_1") (pintype "passive"))
      (node (ref "R4001") (pin "2") (pinfunction "2_2") (pintype "passive"))
      (node (ref "R4003") (pin "1") (pinfunction "1_1") (pintype "passive"))
    )
    (net (code "36") (name "Net-(C4014-Pad1)") (class "Default")
      (node (ref "C4014") (pin "1") (pinfunction "1_1") (pintype "passive"))
      (node (ref "R4004") (pin "2") (pinfunction "2_2") (pintype "passive"))
      (node (ref "R4006") (pin "1") (pinfunction "1_1") (pintype "passive"))
    )
    (net (code "37") (name "Net-(C4015-Pad1)") (class "Default")
      (node (ref "C4015") (pin "1") (pinfunction "1_1") (pintype "passive"))
      (node (ref "R4005") (pin "2") (pinfunction "2_2") (pintype "passive"))
      (node (ref "R4007") (pin "1") (pinfunction "1_1") (pintype "passive"))
    )
    (net (code "38") (name "Net-(C4022-Pad1)") (class "Default")
      (node (ref "C4022") (pin "1") (pinfunction "1_1") (pintype "passive"))
      (node (ref "R4008") (pin "2") (pinfunction "2_2") (pintype "passive"))
      (node (ref "R4010") (pin "1") (pinfunction "1_1") (pintype "passive"))
    )
    (net (code "39") (name "Net-(C4023-Pad1)") (class "Default")
      (node (ref "C4023") (pin "1") (pinfunction "1_1") (pintype "passive"))
      (node (ref "R4009") (pin "2") (pinfunction "2_2") (pintype "passive"))
      (node (ref "R4011") (pin "1") (pinfunction "1_1") (pintype "passive"))
    )
    (net (code "40") (name "Net-(C4030-Pad1)") (class "Default")
      (node (ref "C4030") (pin "1") (pinfunction "1_1") (pintype "passive"))
      (node (ref "R4012") (pin "2") (pinfunction "2_2") (pintype "passive"))
      (node (ref "R4014") (pin "1") (pinfunction "1_1") (pintype "passive"))
    )
    (net (code "41") (name "Net-(C4031-Pad1)") (class "Default")
      (node (ref "C4031") (pin "1") (pinfunction "1_1") (pintype "passive"))
      (node (ref "R4013") (pin "2") (pinfunction "2_2") (pintype "passive"))
      (node (ref "R4015") (pin "1") (pinfunction "1_1") (pintype "passive"))
    )
    (net (code "42") (name "VDD_HV_A") (class "Default")
      (node (ref "C4002") (pin "1") (pinfunction "1_1") (pintype "passive"))
      (node (ref "C4005") (pin "1") (pinfunction "1_1") (pintype "passive"))
      (node (ref "C4010") (pin "1") (pinfunction "1_1") (pintype "passive"))
      (node (ref "C4013") (pin "1") (pinfunction "1_1") (pintype "passive"))
      (node (ref "C4018") (pin "1") (pinfunction "1_1") (pintype "passive"))
      (node (ref "C4021") (pin "1") (pinfunction "1_1") (pintype "passive"))
      (node (ref "C4026") (pin "1") (pinfunction "1_1") (pintype "passive"))
      (node (ref "C4029") (pin "1") (pinfunction "1_1") (pintype "passive"))
      (node (ref "U4000") (pin "5") (pinfunction "VIO_5") (pintype "power_in"))
      (node (ref "U4001") (pin "5") (pinfunction "VIO_5") (pintype "power_in"))
      (node (ref "U4002") (pin "5") (pinfunction "VIO_5") (pintype "power_in"))
      (node (ref "U4003") (pin "5") (pinfunction "VIO_5") (pintype "power_in"))
      (node (ref "U4004") (pin "5") (pinfunction "VIO_5") (pintype "power_in"))
      (node (ref "U4005") (pin "5") (pinfunction "VIO_5") (pintype "power_in"))
      (node (ref "U4006") (pin "5") (pinfunction "VIO_5") (pintype "power_in"))
      (node (ref "U4007") (pin "5") (pinfunction "VIO_5") (pintype "power_in"))
    )
    (net (code "43") (name "VREG_5P0") (class "Default")
      (node (ref "C4000") (pin "1") (pinfunction "1_1") (pintype "passive"))
      (node (ref "C4001") (pin "1") (pinfunction "1_1") (pintype "passive"))
      (node (ref "C4003") (pin "1") (pinfunction "1_1") (pintype "passive"))
      (node (ref "C4004") (pin "1") (pinfunction "1_1") (pintype "passive"))
      (node (ref "C4008") (pin "1") (pinfunction "1_1") (pintype "passive"))
      (node (ref "C4009") (pin "1") (pinfunction "1_1") (pintype "passive"))
      (node (ref "C4011") (pin "1") (pinfunction "1_1") (pintype "passive"))
      (node (ref "C4012") (pin "1") (pinfunction "1_1") (pintype "passive"))
      (node (ref "C4016") (pin "1") (pinfunction "1_1") (pintype "passive"))
      (node (ref "C4017") (pin "1") (pinfunction "1_1") (pintype "passive"))
      (node (ref "C4019") (pin "1") (pinfunction "1_1") (pintype "passive"))
      (node (ref "C4020") (pin "1") (pinfunction "1_1") (pintype "passive"))
      (node (ref "C4024") (pin "1") (pinfunction "1_1") (pintype "passive"))
      (node (ref "C4025") (pin "1") (pinfunction "1_1") (pintype "passive"))
      (node (ref "C4027") (pin "1") (pinfunction "1_1") (pintype "passive"))
      (node (ref "C4028") (pin "1") (pinfunction "1_1") (pintype "passive"))
      (node (ref "U4000") (pin "3") (pinfunction "VCC_3") (pintype "power_in"))
      (node (ref "U4001") (pin "3") (pinfunction "VCC_3") (pintype "power_in"))
      (node (ref "U4002") (pin "3") (pinfunction "VCC_3") (pintype "power_in"))
      (node (ref "U4003") (pin "3") (pinfunction "VCC_3") (pintype "power_in"))
      (node (ref "U4004") (pin "3") (pinfunction "VCC_3") (pintype "power_in"))
      (node (ref "U4005") (pin "3") (pinfunction "VCC_3") (pintype "power_in"))
      (node (ref "U4006") (pin "3") (pinfunction "VCC_3") (pintype "power_in"))
      (node (ref "U4007") (pin "3") (pinfunction "VCC_3") (pintype "power_in"))
    )
  )
)
